# CHRT.net
KiCad netlist of a schematic drawn in Altium Designer
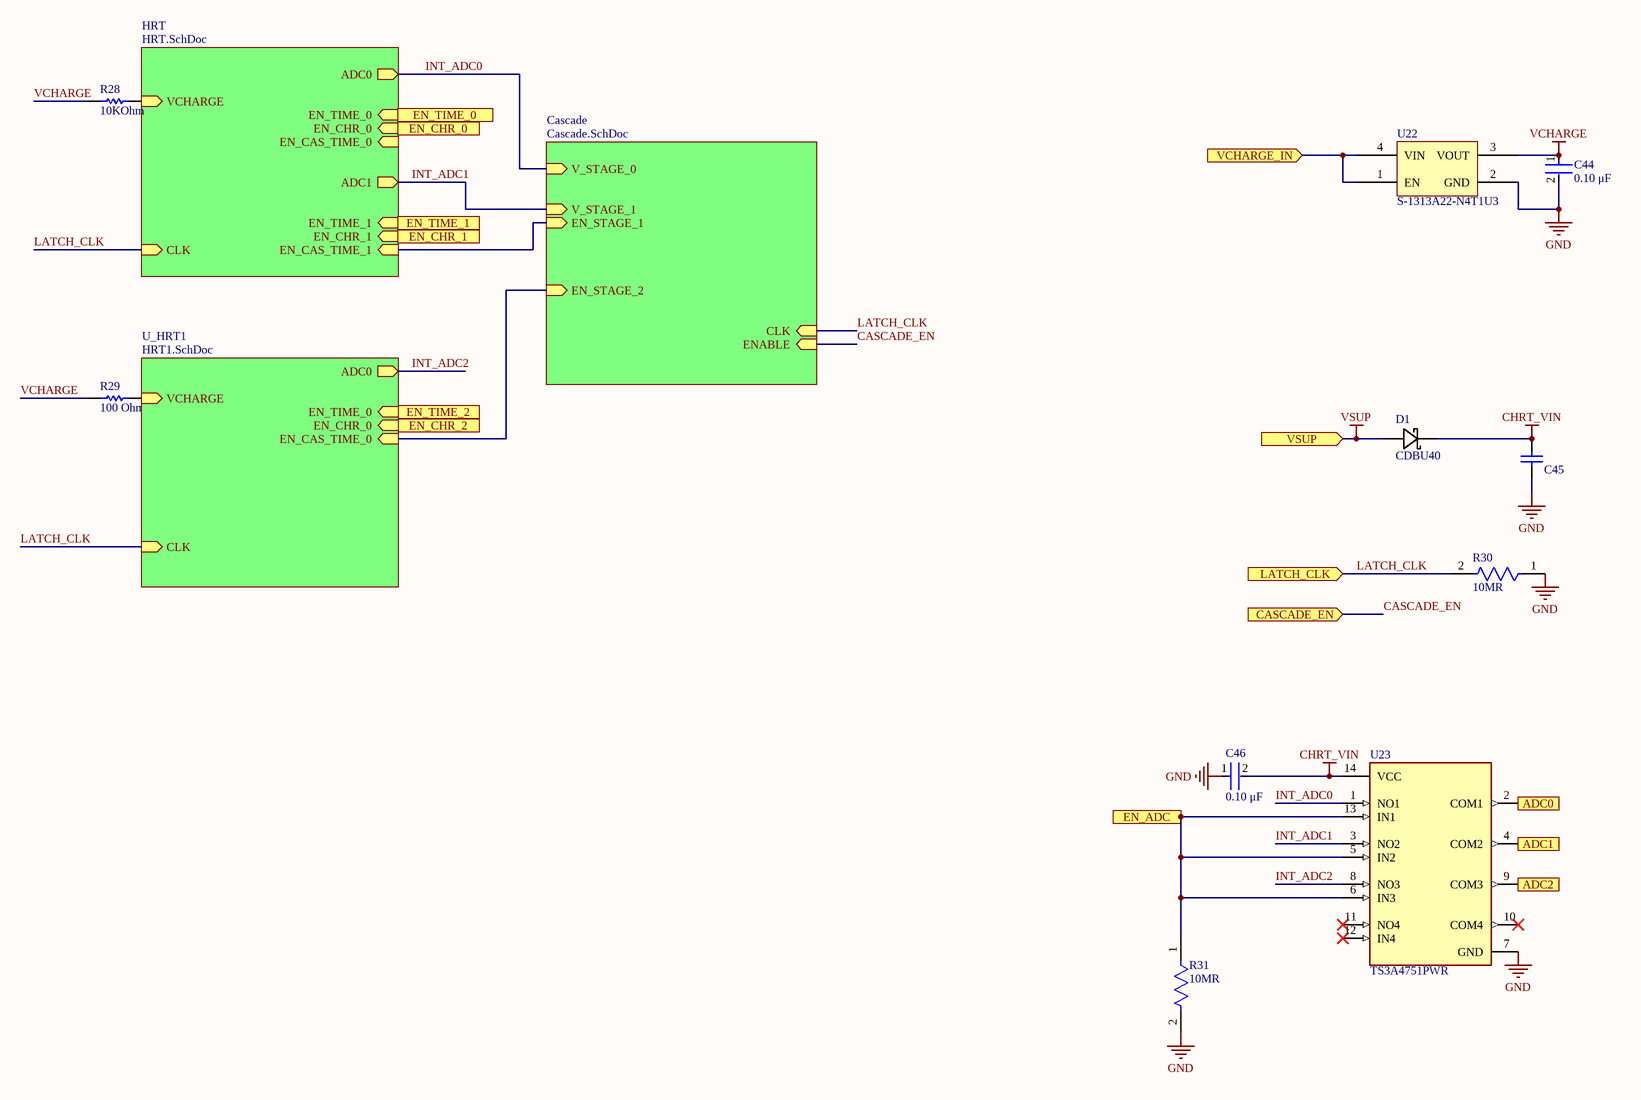
[diagram p0: CHRT.SchDoc]

(export (version "E")
  (design (tool "Eeschema 10.0.6"))
  (components
    (comp (ref "C44")
      (value "C0402C104K8PACTU")
      (footprint "FP-C0402-BB-MFG")
      (description "CAP CER 0.1UF 10V X5R 0402")
      (fields
        (field (name "CAPACITANCE") "0.10 μF")
        (field (name "MANUFACTURER") "Kemet")
        (field (name "TOLERANCE") "0.1")
      )
      (libsource (lib "Altium Content Vault") (part "b4654b650e69147ec39a6b967a45e02"))
    )
    (comp (ref "C45")
      (value "ZRB15XR61A106ME01D")
      (footprint "CAPC1005X55X25NL05T10")
      (fields (field (name "MANUFACTURER") "Murata") (field (name "PART NUMBER") "GRM155R60G106ME44D"))
      (libsource (lib "Altium Content Vault") (part "CAP"))
    )
    (comp (ref "C46")
      (value "C0402C104K8PACTU")
      (footprint "FP-C0402-BB-MFG")
      (description "CAP CER 0.1UF 10V X5R 0402")
      (fields
        (field (name "CAPACITANCE") "0.10 μF")
        (field (name "MANUFACTURER") "Kemet")
        (field (name "TOLERANCE") "0.1")
      )
      (libsource (lib "Altium Content Vault") (part "b4654b650e69147ec39a6b967a45e02"))
    )
    (comp (ref "D1")
      (value "CDBU40")
      (footprint "CDBU")
      (description "No Description Available")
      (fields (field (name "COPYRIGHT") "Copyright (C) 2022 Ultra Librarian. All rights reserved."))
      (libsource (lib "CDBU40") (part "CDBU40"))
    )
    (comp (ref "R28")
      (value "RMCF0402FT10K0")
      (footprint "RESC1005X40X25LL05T05")
      (description "Chip Resistor, 10 KOhm, +/- 1%, 0.1 W, -55 to 155 degC, 0402 (1005 Metric), RoHS, Tape and Reel")
      (fields
        (field (name "RESISTANCE") "10KOhm")
        (field (name "TOLERANCE") "1%")
        (field (name "MANUFACTURER") "Panasonic")
      )
      (libsource (lib "Altium Content Vault") (part "RES-2"))
    )
    (comp (ref "R29")
      (value "ERJ-2RKF1000X")
      (footprint "RESC1005X40X25LL05T05")
      (description "Chip Resistor, 100 Ohm, +/- 1%, 100 mW, -55 to 155 degC, 0402 (1005 Metric), RoHS, Tape and Reel")
      (fields
        (field (name "MANUFACTURER") "Basic Passives")
        (field (name "TOLERANCE") "1%")
        (field (name "RESISTANCE") "100 Ohm")
      )
      (libsource (lib "Altium Content Vault") (part "RES-2"))
    )
    (comp (ref "R30")
      (value "CRCW040210M0JNED")
      (footprint "FP-CRCW0402-e3-IPC_C")
      (description "RES Thick Film, 10MΩ, 5%, 0.063W, 200ppm/°C, 0402")
      (fields (field (name "TOLERANCE") "5%") (field (name "RESISTANCE") "10MR"))
      (libsource (lib "Altium Content Vault") (part "1029c3af85768c4190bb7ad29bc67b5"))
    )
    (comp (ref "R31")
      (value "CRCW040210M0JNED")
      (footprint "FP-CRCW0402-e3-IPC_C")
      (description "RES Thick Film, 10MΩ, 5%, 0.063W, 200ppm/°C, 0402")
      (fields (field (name "TOLERANCE") "5%") (field (name "RESISTANCE") "10MR"))
      (libsource (lib "Altium Content Vault") (part "1029c3af85768c4190bb7ad29bc67b5"))
    )
    (comp (ref "U22")
      (value "S-1313A22-N4T1U3")
      (footprint "SOT130P210X110-4N")
      (libsource (lib "Integrated_Library1") (part "S-1313A22-N4T1U3"))
    )
    (comp (ref "U23")
      (value "TS3A4751PWR")
      (footprint "FP-PW0014A-IPC_C")
      (description "IC SWITCH QUAD SPST 14TSSOP")
      (libsource (lib "Altium Content Vault") (part "75fdcfb842d41a92b92a478e82e68ae"))
    )
  )
  (nets
    (net (code "1") (name "/ADC0") (class "Default")
      (node (ref "U23") (pin "2") (pinfunction "COM1_2") (pintype "output"))
    )
    (net (code "2") (name "/ADC1") (class "Default")
      (node (ref "U23") (pin "4") (pinfunction "COM2_4") (pintype "output"))
    )
    (net (code "3") (name "/ADC2") (class "Default")
      (node (ref "U23") (pin "9") (pinfunction "COM3_9") (pintype "output"))
    )
    (net (code "5") (name "/EN_ADC") (class "Default")
      (node (ref "R31") (pin "1") (pinfunction "1_1") (pintype "passive"))
      (node (ref "U23") (pin "13") (pinfunction "IN1_13") (pintype "input"))
      (node (ref "U23") (pin "5") (pinfunction "IN2_5") (pintype "input"))
      (node (ref "U23") (pin "6") (pinfunction "IN3_6") (pintype "input"))
    )
    (net (code "15") (name "/INT_ADC0") (class "Default")
      (node (ref "U23") (pin "1") (pinfunction "NO1_1") (pintype "input"))
    )
    (net (code "16") (name "/INT_ADC1") (class "Default")
      (node (ref "U23") (pin "3") (pinfunction "NO2_3") (pintype "input"))
    )
    (net (code "17") (name "/INT_ADC2") (class "Default")
      (node (ref "U23") (pin "8") (pinfunction "NO3_8") (pintype "input"))
    )
    (net (code "18") (name "/LATCH_CLK") (class "Default")
      (node (ref "R30") (pin "2") (pinfunction "2_2") (pintype "passive"))
    )
    (net (code "19") (name "/VCHARGE_1") (class "Default")
      (node (ref "R29") (pin "2") (pinfunction "2_2") (pintype "passive"))
    )
    (net (code "20") (name "/VCHARGE_2") (class "Default")
      (node (ref "R28") (pin "2") (pinfunction "2_2") (pintype "passive"))
    )
    (net (code "21") (name "/VCHARGE_IN") (class "Default")
      (node (ref "U22") (pin "1") (pinfunction "EN_1") (pintype "passive"))
      (node (ref "U22") (pin "4") (pinfunction "VIN_4") (pintype "passive"))
    )
    (net (code "22") (name "CHRT_VIN") (class "Default")
      (node (ref "C45") (pin "2") (pinfunction "2_2") (pintype "passive"))
      (node (ref "C46") (pin "2") (pinfunction "2_2") (pintype "passive"))
      (node (ref "D1") (pin "1") (pinfunction "1_1") (pintype "passive"))
      (node (ref "U23") (pin "14") (pinfunction "VCC_14") (pintype "power_in"))
    )
    (net (code "23") (name "GND") (class "Default")
      (node (ref "C44") (pin "2") (pinfunction "2_2") (pintype "passive"))
      (node (ref "C45") (pin "1") (pinfunction "1_1") (pintype "passive"))
      (node (ref "C46") (pin "1") (pinfunction "1_1") (pintype "passive"))
      (node (ref "R30") (pin "1") (pinfunction "1_1") (pintype "passive"))
      (node (ref "R31") (pin "2") (pinfunction "2_2") (pintype "passive"))
      (node (ref "U22") (pin "2") (pinfunction "GND_2") (pintype "passive"))
      (node (ref "U23") (pin "7") (pinfunction "GND_7") (pintype "power_in"))
    )
    (net (code "24") (name "VCHARGE") (class "Default")
      (node (ref "C44") (pin "1") (pinfunction "1_1") (pintype "passive"))
      (node (ref "R28") (pin "1") (pinfunction "1_1") (pintype "passive"))
      (node (ref "R29") (pin "1") (pinfunction "1_1") (pintype "passive"))
      (node (ref "U22") (pin "3") (pinfunction "VOUT_3") (pintype "passive"))
    )
    (net (code "25") (name "VSUP") (class "Default")
      (node (ref "D1") (pin "2") (pinfunction "2_2") (pintype "passive"))
    )
    (net (code "26") (name "unconnected-(U23-COM4-Pad10)") (class "Default")
      (node (ref "U23") (pin "10") (pinfunction "COM4_10") (pintype "output+no_connect"))
    )
    (net (code "27") (name "unconnected-(U23-IN4-Pad12)") (class "Default")
      (node (ref "U23") (pin "12") (pinfunction "IN4_12") (pintype "input+no_connect"))
    )
    (net (code "28") (name "unconnected-(U23-NO4-Pad11)") (class "Default")
      (node (ref "U23") (pin "11") (pinfunction "NO4_11") (pintype "input+no_connect"))
    )
  )
)
